# ethernet.net
KiCad netlist of a schematic drawn in Altium Designer
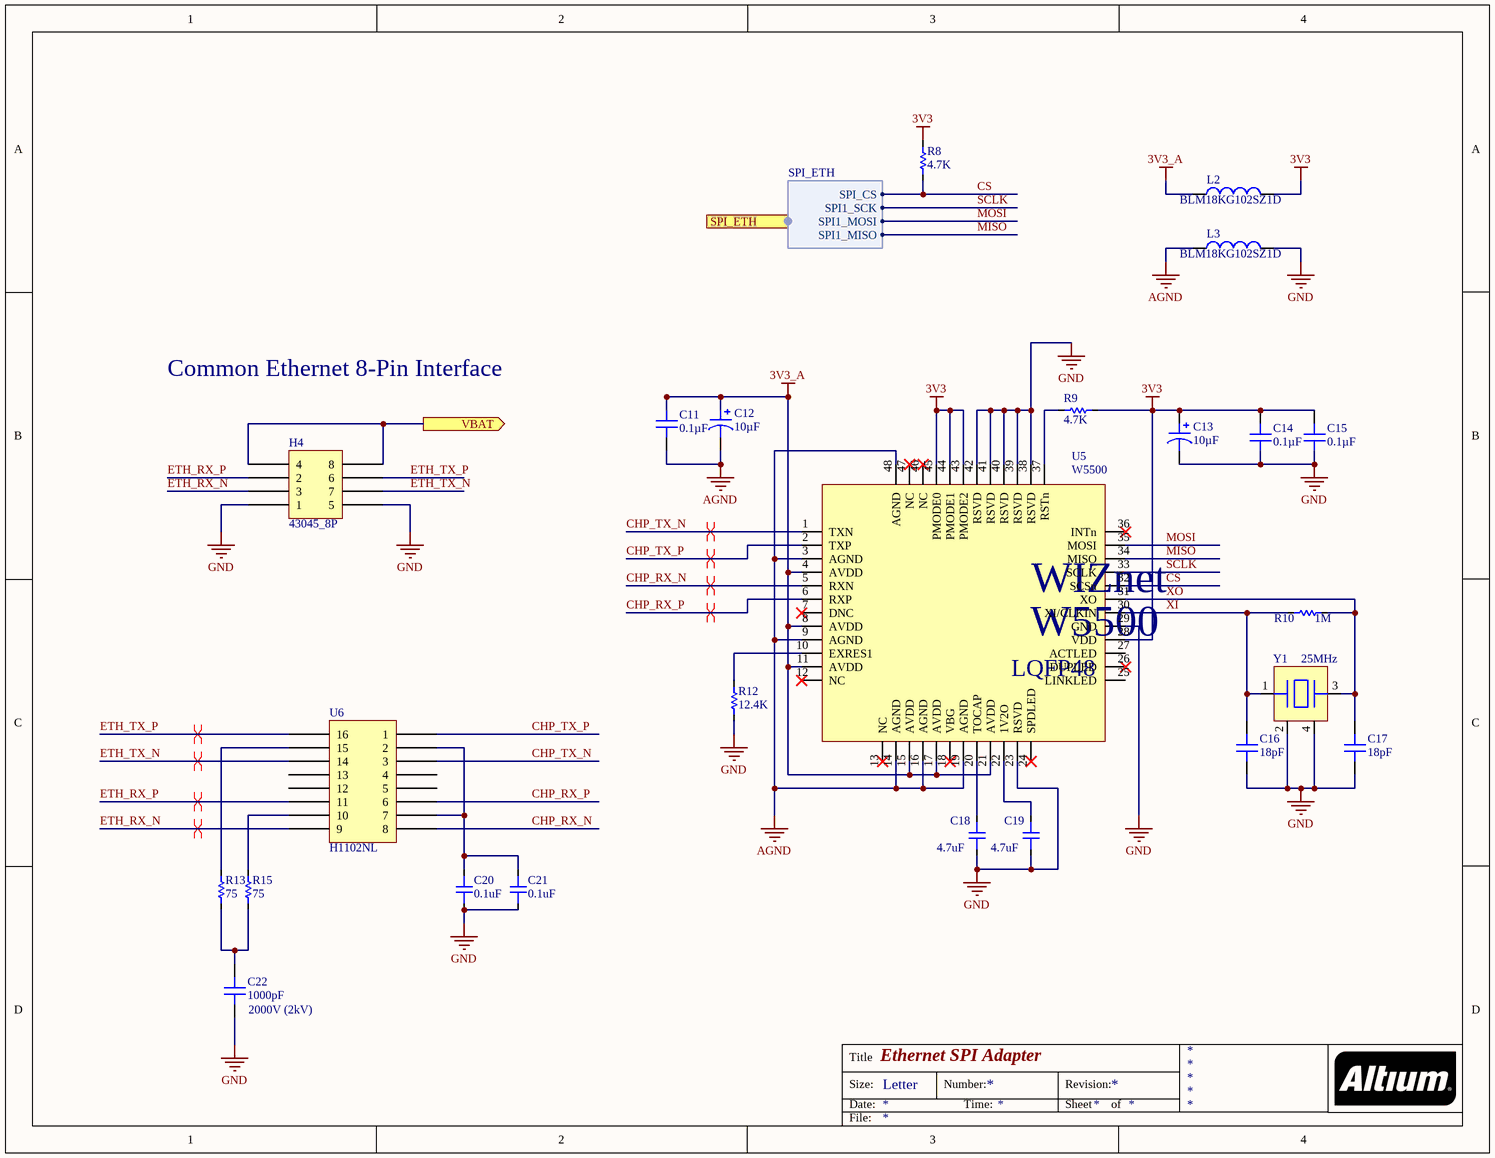
[diagram p0: ethernet.SchDoc]

(export (version "E")
  (design (tool "Eeschema 10.0.6"))
  (components
    (comp (ref "C11")
      (value "0.1µF")
      (footprint "CAP 0603_1608")
      (description "CAP CER 0.1UF 50V X7R 0603")
      (fields (field (name "PART NUMBER") "C0603C104K5RACAUTO") (field (name "MANUFACTURER") "KEMET"))
      (libsource (lib "Celestial Altium Library - altium_library") (part "Capacitor"))
    )
    (comp (ref "C12")
      (value "10µF")
      (footprint "CAP POL 1411_3528")
      (description "CAP TANT 10UF 10% 16V 1411")
      (fields (field (name "PART NUMBER") "T491B106K016ATAUTO") (field (name "MANUFACTURER") "KEMET"))
      (libsource (lib "Celestial Altium Library - altium_library") (part "Polarised Capacitor"))
    )
    (comp (ref "C13")
      (value "10µF")
      (footprint "CAP POL 1411_3528")
      (description "CAP TANT 10UF 10% 16V 1411")
      (fields (field (name "PART NUMBER") "T491B106K016ATAUTO") (field (name "MANUFACTURER") "KEMET"))
      (libsource (lib "Celestial Altium Library - altium_library") (part "Polarised Capacitor"))
    )
    (comp (ref "C14")
      (value "0.1µF")
      (footprint "CAP 0603_1608")
      (description "CAP CER 0.1UF 50V X7R 0603")
      (fields (field (name "PART NUMBER") "C0603C104K5RACAUTO") (field (name "MANUFACTURER") "KEMET"))
      (libsource (lib "Celestial Altium Library - altium_library") (part "Capacitor"))
    )
    (comp (ref "C15")
      (value "0.1µF")
      (footprint "CAP 0603_1608")
      (description "CAP CER 0.1UF 50V X7R 0603")
      (fields (field (name "PART NUMBER") "C0603C104K5RACAUTO") (field (name "MANUFACTURER") "KEMET"))
      (libsource (lib "Celestial Altium Library - altium_library") (part "Capacitor"))
    )
    (comp (ref "C16")
      (value "18pF")
      (footprint "CAP 0603_1608")
      (description "CAP CER 18PF 50V C0G/NP0 0603")
      (fields (field (name "PART NUMBER") "C0603C180J5GACAUTO") (field (name "MANUFACTURER") "KEMET"))
      (libsource (lib "Celestial Altium Library - altium_library") (part "Capacitor"))
    )
    (comp (ref "C17")
      (value "18pF")
      (footprint "CAP 0603_1608")
      (description "CAP CER 18PF 50V C0G/NP0 0603")
      (fields (field (name "PART NUMBER") "C0603C180J5GACAUTO") (field (name "MANUFACTURER") "KEMET"))
      (libsource (lib "Celestial Altium Library - altium_library") (part "Capacitor"))
    )
    (comp (ref "C18")
      (value "4.7uF")
      (footprint "CAP 0805 L")
      (description "Cap Ceramic 4.7uF 16V X7R 10% Pad SMD 0805 125C Automotive T/R")
      (fields
        (field (name "MANUFACTURER") "KEMET")
        (field (name "MANUFACTURER PART NUMBER") "C0805C475K4RACAUTO")
      )
      (libsource (lib "streetbot") (part "CAP 0805"))
    )
    (comp (ref "C19")
      (value "4.7uF")
      (footprint "CAP 0805 L")
      (description "Cap Ceramic 4.7uF 16V X7R 10% Pad SMD 0805 125C Automotive T/R")
      (fields
        (field (name "MANUFACTURER") "KEMET")
        (field (name "MANUFACTURER PART NUMBER") "C0805C475K4RACAUTO")
      )
      (libsource (lib "streetbot") (part "CAP 0805"))
    )
    (comp (ref "C20")
      (value "0.1uF")
      (footprint "CAP 0805 L")
      (description "Cap Ceramic 0.01uF 100V X7R 10% SMD 0805 125C Paper T/R")
      (fields
        (field (name "MANUFACTURER") "KEMET")
        (field (name "MANUFACTURER PART NUMBER") "C0805C103K1RACAUTO")
      )
      (libsource (lib "streetbot") (part "CAP 0805"))
    )
    (comp (ref "C21")
      (value "0.1uF")
      (footprint "CAP 0805 L")
      (description "Cap Ceramic 0.01uF 100V X7R 10% SMD 0805 125C Paper T/R")
      (fields
        (field (name "MANUFACTURER") "KEMET")
        (field (name "MANUFACTURER PART NUMBER") "C0805C103K1RACAUTO")
      )
      (libsource (lib "streetbot") (part "CAP 0805"))
    )
    (comp (ref "C22")
      (value "1000pF")
      (footprint "CAP 1206_3216 - 1.8MM")
      (description "CAP CER 1000PF 2KV X7R 1206")
      (fields
        (field (name "PART NUMBER") "C1206C102KGRACAUTO")
        (field (name "MANUFACTURER") "KEMET")
        (field (name "VOLTAGE - RATED") "2000V (2kV)")
      )
      (libsource (lib "Celestial Altium Library - altium_library") (part "Capacitor"))
    )
    (comp (ref "H4")
      (value "43045_8P")
      (footprint "MOLEX_43045_2X4")
      (libsource (lib "food_box") (part "TERM_2x4P"))
    )
    (comp (ref "L2")
      (value "BLM18KG102SZ1D")
      (footprint "IND-0603")
      (description "Ferrite Beads Multi-Layer Power 1KOhm 25% 100MHz 1A 200mOhm DCR 0603 Automotive T/R")
      (fields (field (name "MANUFACTURER") "Murata"))
      (libsource (lib "food_box") (part "IND-0603"))
    )
    (comp (ref "L3")
      (value "BLM18KG102SZ1D")
      (footprint "IND-0603")
      (description "Ferrite Beads Multi-Layer Power 1KOhm 25% 100MHz 1A 200mOhm DCR 0603 Automotive T/R")
      (fields (field (name "MANUFACTURER") "Murata"))
      (libsource (lib "food_box") (part "IND-0603"))
    )
    (comp (ref "R8")
      (value "4.7K")
      (footprint "RES 0603 L")
      (description "SMD Resistor, Thick film 4.7 kOhm,  ±  1 %, 0603, CRCW06034K70FKEA, Vishay")
      (fields
        (field (name "MANUFACTURER") "Vishay")
        (field (name "MANUFACTURER PART NUMBER") "CRCW06034K70FKEA")
      )
      (libsource (lib "streetbot") (part "RES 0603"))
    )
    (comp (ref "R9")
      (value "4.7K")
      (footprint "RES 0603 L")
      (description "SMD Resistor, Thick film 4.7 kOhm,  ±  1 %, 0603, CRCW06034K70FKEA, Vishay")
      (fields
        (field (name "MANUFACTURER") "Vishay")
        (field (name "MANUFACTURER PART NUMBER") "CRCW06034K70FKEA")
      )
      (libsource (lib "streetbot") (part "RES 0603"))
    )
    (comp (ref "R10")
      (value "1M")
      (footprint "RES 0603 L")
      (description "Thick Film Chip Resistor")
      (fields
        (field (name "MANUFACTURER") "Vishay")
        (field (name "MANUFACTURER PART NUMBER") "CRCW06031M00FKEA")
      )
      (libsource (lib "streetbot") (part "RES 0603"))
    )
    (comp (ref "R12")
      (value "12.4K")
      (footprint "RES 0603 L")
      (description "Res Thick Film 0603 12.4K Ohm 1% 1/10W ±100ppm/°C Molded SMD SMD Paper T/R")
      (fields
        (field (name "MANUFACTURER") "Vishay")
        (field (name "MANUFACTURER PART NUMBER") "CRCW0603-12K4FKEA")
      )
      (libsource (lib "streetbot") (part "RES 0603"))
    )
    (comp (ref "R13")
      (value "75")
      (footprint "RES 0603 L")
      (description "VISHAY - CRCW060375R0FKEA - RES, 75R, 1%, 0.1W, 0603, THICK FILM")
      (fields
        (field (name "MANUFACTURER") "Vishay")
        (field (name "MANUFACTURER PART NUMBER") "CRCW060375R0FKEA")
      )
      (libsource (lib "streetbot") (part "RES 0603"))
    )
    (comp (ref "R15")
      (value "75")
      (footprint "RES 0603 L")
      (description "VISHAY - CRCW060375R0FKEA - RES, 75R, 1%, 0.1W, 0603, THICK FILM")
      (fields
        (field (name "MANUFACTURER") "Vishay")
        (field (name "MANUFACTURER PART NUMBER") "CRCW060375R0FKEA")
      )
      (libsource (lib "streetbot") (part "RES 0603"))
    )
    (comp (ref "U5")
      (value "W5500")
      (footprint "WIZNET W5500")
      (description "WIZnet W5500")
      (libsource (lib "WIZnet Open-source Hardware Library V1.0") (part "W5500"))
    )
    (comp (ref "U6") (value "H1102NL") (footprint "H1102NL") (libsource (lib "food_box") (part "H1102NL")))
    (comp (ref "Y1")
      (value "25MHz")
      (footprint "OSC-82J0626")
      (description "CRYSTAL 25.0000MHZ 18PF SMD")
      (fields
        (field (name "MANUFACTURER") "Epson")
        (field (name "MANUFACTURER PART NUMBER") "FA-23825.0000MB-C3")
      )
      (libsource (lib "food_box") (part "OSC-82J0626-25MHz"))
    )
  )
  (nets
    (net (code "2") (name "/CHP_RX_N") (class "Default")
      (node (ref "U5") (pin "5") (pinfunction "RXN_5") (pintype "passive"))
      (node (ref "U6") (pin "8") (pinfunction "8_8") (pintype "passive"))
    )
    (net (code "3") (name "/CHP_RX_P") (class "Default")
      (node (ref "U5") (pin "6") (pinfunction "RXP_6") (pintype "passive"))
      (node (ref "U6") (pin "6") (pinfunction "6_6") (pintype "passive"))
    )
    (net (code "4") (name "/CHP_TX_N") (class "Default")
      (node (ref "U5") (pin "1") (pinfunction "TXN_1") (pintype "passive"))
      (node (ref "U6") (pin "3") (pinfunction "3_3") (pintype "passive"))
    )
    (net (code "5") (name "/CHP_TX_P") (class "Default")
      (node (ref "U5") (pin "2") (pinfunction "TXP_2") (pintype "passive"))
      (node (ref "U6") (pin "1") (pinfunction "1_1") (pintype "passive"))
    )
    (net (code "6") (name "/CS") (class "Default")
      (node (ref "R8") (pin "1") (pinfunction "1_1") (pintype "passive"))
      (node (ref "U5") (pin "32") (pinfunction "SCSn_32") (pintype "passive"))
    )
    (net (code "7") (name "/ETH_RX_N") (class "Default")
      (node (ref "H4") (pin "3") (pinfunction "3_3") (pintype "passive"))
      (node (ref "U6") (pin "9") (pinfunction "9_9") (pintype "passive"))
    )
    (net (code "8") (name "/ETH_RX_P") (class "Default")
      (node (ref "H4") (pin "2") (pinfunction "2_2") (pintype "passive"))
      (node (ref "U6") (pin "11") (pinfunction "11_11") (pintype "passive"))
    )
    (net (code "9") (name "/ETH_TX_N") (class "Default")
      (node (ref "H4") (pin "7") (pinfunction "7_7") (pintype "passive"))
      (node (ref "U6") (pin "14") (pinfunction "14_14") (pintype "passive"))
    )
    (net (code "10") (name "/ETH_TX_P") (class "Default")
      (node (ref "H4") (pin "6") (pinfunction "6_6") (pintype "passive"))
      (node (ref "U6") (pin "16") (pinfunction "16_16") (pintype "passive"))
    )
    (net (code "11") (name "/MISO") (class "Default")
      (node (ref "U5") (pin "34") (pinfunction "MISO_34") (pintype "passive"))
    )
    (net (code "12") (name "/MOSI") (class "Default")
      (node (ref "U5") (pin "35") (pinfunction "MOSI_35") (pintype "passive"))
    )
    (net (code "13") (name "/SCLK") (class "Default")
      (node (ref "U5") (pin "33") (pinfunction "SCLK_33") (pintype "passive"))
    )
    (net (code "14") (name "/VBAT") (class "Default")
      (node (ref "H4") (pin "4") (pinfunction "4_4") (pintype "passive"))
      (node (ref "H4") (pin "8") (pinfunction "8_8") (pintype "passive"))
    )
    (net (code "15") (name "/XI") (class "Default")
      (node (ref "C16") (pin "2") (pinfunction "2_2") (pintype "passive"))
      (node (ref "R10") (pin "1") (pinfunction "1_1") (pintype "passive"))
      (node (ref "U5") (pin "30") (pinfunction "XI/CLKIN_30") (pintype "passive"))
      (node (ref "Y1") (pin "1") (pinfunction "1_1") (pintype "passive"))
    )
    (net (code "16") (name "/XO") (class "Default")
      (node (ref "C17") (pin "2") (pinfunction "2_2") (pintype "passive"))
      (node (ref "R10") (pin "2") (pinfunction "2_2") (pintype "passive"))
      (node (ref "U5") (pin "31") (pinfunction "XO_31") (pintype "passive"))
      (node (ref "Y1") (pin "3") (pinfunction "3_3") (pintype "passive"))
    )
    (net (code "18") (name "3V3") (class "Default")
      (node (ref "C13") (pin "1") (pinfunction "1_1") (pintype "passive"))
      (node (ref "C14") (pin "2") (pinfunction "2_2") (pintype "passive"))
      (node (ref "C15") (pin "2") (pinfunction "2_2") (pintype "passive"))
      (node (ref "L2") (pin "2") (pinfunction "2_2") (pintype "passive"))
      (node (ref "R8") (pin "2") (pinfunction "2_2") (pintype "passive"))
      (node (ref "R9") (pin "2") (pinfunction "2_2") (pintype "passive"))
      (node (ref "U5") (pin "28") (pinfunction "VDD_28") (pintype "passive"))
      (node (ref "U5") (pin "43") (pinfunction "PMODE2_43") (pintype "passive"))
      (node (ref "U5") (pin "44") (pinfunction "PMODE1_44") (pintype "passive"))
      (node (ref "U5") (pin "45") (pinfunction "PMODE0_45") (pintype "passive"))
    )
    (net (code "19") (name "3V3_A") (class "Default")
      (node (ref "C11") (pin "2") (pinfunction "2_2") (pintype "passive"))
      (node (ref "C12") (pin "1") (pinfunction "1_1") (pintype "passive"))
      (node (ref "L2") (pin "1") (pinfunction "1_1") (pintype "passive"))
      (node (ref "U5") (pin "11") (pinfunction "AVDD_11") (pintype "passive"))
      (node (ref "U5") (pin "15") (pinfunction "AVDD_15") (pintype "passive"))
      (node (ref "U5") (pin "17") (pinfunction "AVDD_17") (pintype "passive"))
      (node (ref "U5") (pin "21") (pinfunction "AVDD_21") (pintype "passive"))
      (node (ref "U5") (pin "4") (pinfunction "AVDD_4") (pintype "passive"))
      (node (ref "U5") (pin "8") (pinfunction "AVDD_8") (pintype "passive"))
    )
    (net (code "20") (name "AGND") (class "Default")
      (node (ref "C11") (pin "1") (pinfunction "1_1") (pintype "passive"))
      (node (ref "C12") (pin "2") (pinfunction "2_2") (pintype "passive"))
      (node (ref "L3") (pin "1") (pinfunction "1_1") (pintype "passive"))
      (node (ref "U5") (pin "14") (pinfunction "AGND_14") (pintype "passive"))
      (node (ref "U5") (pin "16") (pinfunction "AGND_16") (pintype "passive"))
      (node (ref "U5") (pin "19") (pinfunction "AGND_19") (pintype "passive"))
      (node (ref "U5") (pin "3") (pinfunction "AGND_3") (pintype "passive"))
      (node (ref "U5") (pin "48") (pinfunction "AGND_48") (pintype "passive"))
      (node (ref "U5") (pin "9") (pinfunction "AGND_9") (pintype "passive"))
    )
    (net (code "21") (name "GND") (class "Default")
      (node (ref "C13") (pin "2") (pinfunction "2_2") (pintype "passive"))
      (node (ref "C14") (pin "1") (pinfunction "1_1") (pintype "passive"))
      (node (ref "C15") (pin "1") (pinfunction "1_1") (pintype "passive"))
      (node (ref "C16") (pin "1") (pinfunction "1_1") (pintype "passive"))
      (node (ref "C17") (pin "1") (pinfunction "1_1") (pintype "passive"))
      (node (ref "C18") (pin "1") (pinfunction "1_1") (pintype "passive"))
      (node (ref "C19") (pin "1") (pinfunction "1_1") (pintype "passive"))
      (node (ref "C20") (pin "1") (pinfunction "1_1") (pintype "passive"))
      (node (ref "C21") (pin "1") (pinfunction "1_1") (pintype "passive"))
      (node (ref "C22") (pin "1") (pinfunction "1_1") (pintype "passive"))
      (node (ref "H4") (pin "1") (pinfunction "1_1") (pintype "passive"))
      (node (ref "H4") (pin "5") (pinfunction "5_5") (pintype "passive"))
      (node (ref "L3") (pin "2") (pinfunction "2_2") (pintype "passive"))
      (node (ref "R12") (pin "1") (pinfunction "1_1") (pintype "passive"))
      (node (ref "U5") (pin "23") (pinfunction "RSVD_23") (pintype "passive"))
      (node (ref "U5") (pin "29") (pinfunction "GND_29") (pintype "passive"))
      (node (ref "U5") (pin "38") (pinfunction "RSVD_38") (pintype "passive"))
      (node (ref "U5") (pin "39") (pinfunction "RSVD_39") (pintype "passive"))
      (node (ref "U5") (pin "40") (pinfunction "RSVD_40") (pintype "passive"))
      (node (ref "U5") (pin "41") (pinfunction "RSVD_41") (pintype "passive"))
      (node (ref "U5") (pin "42") (pinfunction "RSVD_42") (pintype "passive"))
      (node (ref "Y1") (pin "2") (pinfunction "2_2") (pintype "passive"))
      (node (ref "Y1") (pin "4") (pinfunction "4_4") (pintype "passive"))
    )
    (net (code "22") (name "Net-(C20-Pad2)") (class "Default")
      (node (ref "C20") (pin "2") (pinfunction "2_2") (pintype "passive"))
      (node (ref "C21") (pin "2") (pinfunction "2_2") (pintype "passive"))
      (node (ref "U6") (pin "2") (pinfunction "2_2") (pintype "passive"))
      (node (ref "U6") (pin "7") (pinfunction "7_7") (pintype "passive"))
    )
    (net (code "23") (name "Net-(C22-Pad2)") (class "Default")
      (node (ref "C22") (pin "2") (pinfunction "2_2") (pintype "passive"))
      (node (ref "R13") (pin "1") (pinfunction "1_1") (pintype "passive"))
      (node (ref "R15") (pin "1") (pinfunction "1_1") (pintype "passive"))
    )
    (net (code "24") (name "Net-(R13-Pad2)") (class "Default")
      (node (ref "R13") (pin "2") (pinfunction "2_2") (pintype "passive"))
      (node (ref "U6") (pin "15") (pinfunction "15_15") (pintype "passive"))
    )
    (net (code "25") (name "Net-(R15-Pad2)") (class "Default")
      (node (ref "R15") (pin "2") (pinfunction "2_2") (pintype "passive"))
      (node (ref "U6") (pin "10") (pinfunction "10_10") (pintype "passive"))
    )
    (net (code "26") (name "Net-(U5-1V2O)") (class "Default")
      (node (ref "C19") (pin "2") (pinfunction "2_2") (pintype "passive"))
      (node (ref "U5") (pin "22") (pinfunction "1V2O_22") (pintype "passive"))
    )
    (net (code "27") (name "Net-(U5-EXRES1)") (class "Default")
      (node (ref "R12") (pin "2") (pinfunction "2_2") (pintype "passive"))
      (node (ref "U5") (pin "10") (pinfunction "EXRES1_10") (pintype "passive"))
    )
    (net (code "28") (name "Net-(U5-RSTn)") (class "Default")
      (node (ref "R9") (pin "1") (pinfunction "1_1") (pintype "passive"))
      (node (ref "U5") (pin "37") (pinfunction "RSTn_37") (pintype "passive"))
    )
    (net (code "29") (name "Net-(U5-TOCAP)") (class "Default")
      (node (ref "C18") (pin "2") (pinfunction "2_2") (pintype "passive"))
      (node (ref "U5") (pin "20") (pinfunction "TOCAP_20") (pintype "passive"))
    )
    (net (code "30") (name "unconnected-(U5-ACTLED-Pad27)") (class "Default")
      (node (ref "U5") (pin "27") (pinfunction "ACTLED_27") (pintype "passive"))
    )
    (net (code "31") (name "unconnected-(U5-DNC-Pad7)") (class "Default")
      (node (ref "U5") (pin "7") (pinfunction "DNC_7") (pintype "passive+no_connect"))
    )
    (net (code "32") (name "unconnected-(U5-DUPLED-Pad26)") (class "Default")
      (node (ref "U5") (pin "26") (pinfunction "DUPLED_26") (pintype "passive+no_connect"))
    )
    (net (code "33") (name "unconnected-(U5-INTn-Pad36)") (class "Default")
      (node (ref "U5") (pin "36") (pinfunction "INTn_36") (pintype "passive+no_connect"))
    )
    (net (code "34") (name "unconnected-(U5-LINKLED-Pad25)") (class "Default")
      (node (ref "U5") (pin "25") (pinfunction "LINKLED_25") (pintype "passive"))
    )
    (net (code "35") (name "unconnected-(U5-NC-Pad12)") (class "Default")
      (node (ref "U5") (pin "12") (pinfunction "NC_12") (pintype "passive+no_connect"))
    )
    (net (code "36") (name "unconnected-(U5-NC-Pad13)") (class "Default")
      (node (ref "U5") (pin "13") (pinfunction "NC_13") (pintype "passive+no_connect"))
    )
    (net (code "37") (name "unconnected-(U5-NC-Pad46)") (class "Default")
      (node (ref "U5") (pin "46") (pinfunction "NC_46") (pintype "passive+no_connect"))
    )
    (net (code "38") (name "unconnected-(U5-NC-Pad47)") (class "Default")
      (node (ref "U5") (pin "47") (pinfunction "NC_47") (pintype "passive+no_connect"))
    )
    (net (code "39") (name "unconnected-(U5-SPDLED-Pad24)") (class "Default")
      (node (ref "U5") (pin "24") (pinfunction "SPDLED_24") (pintype "passive+no_connect"))
    )
    (net (code "40") (name "unconnected-(U5-VBG-Pad18)") (class "Default")
      (node (ref "U5") (pin "18") (pinfunction "VBG_18") (pintype "passive+no_connect"))
    )
    (net (code "41") (name "unconnected-(U6-Pad4)") (class "Default")
      (node (ref "U6") (pin "4") (pinfunction "4_4") (pintype "passive"))
    )
    (net (code "42") (name "unconnected-(U6-Pad5)") (class "Default")
      (node (ref "U6") (pin "5") (pinfunction "5_5") (pintype "passive"))
    )
    (net (code "43") (name "unconnected-(U6-Pad12)") (class "Default")
      (node (ref "U6") (pin "12") (pinfunction "12_12") (pintype "passive"))
    )
    (net (code "44") (name "unconnected-(U6-Pad13)") (class "Default")
      (node (ref "U6") (pin "13") (pinfunction "13_13") (pintype "passive"))
    )
  )
)
